# time_circuit_controller_1_1.net
KiCad netlist of a schematic drawn in EAGLE
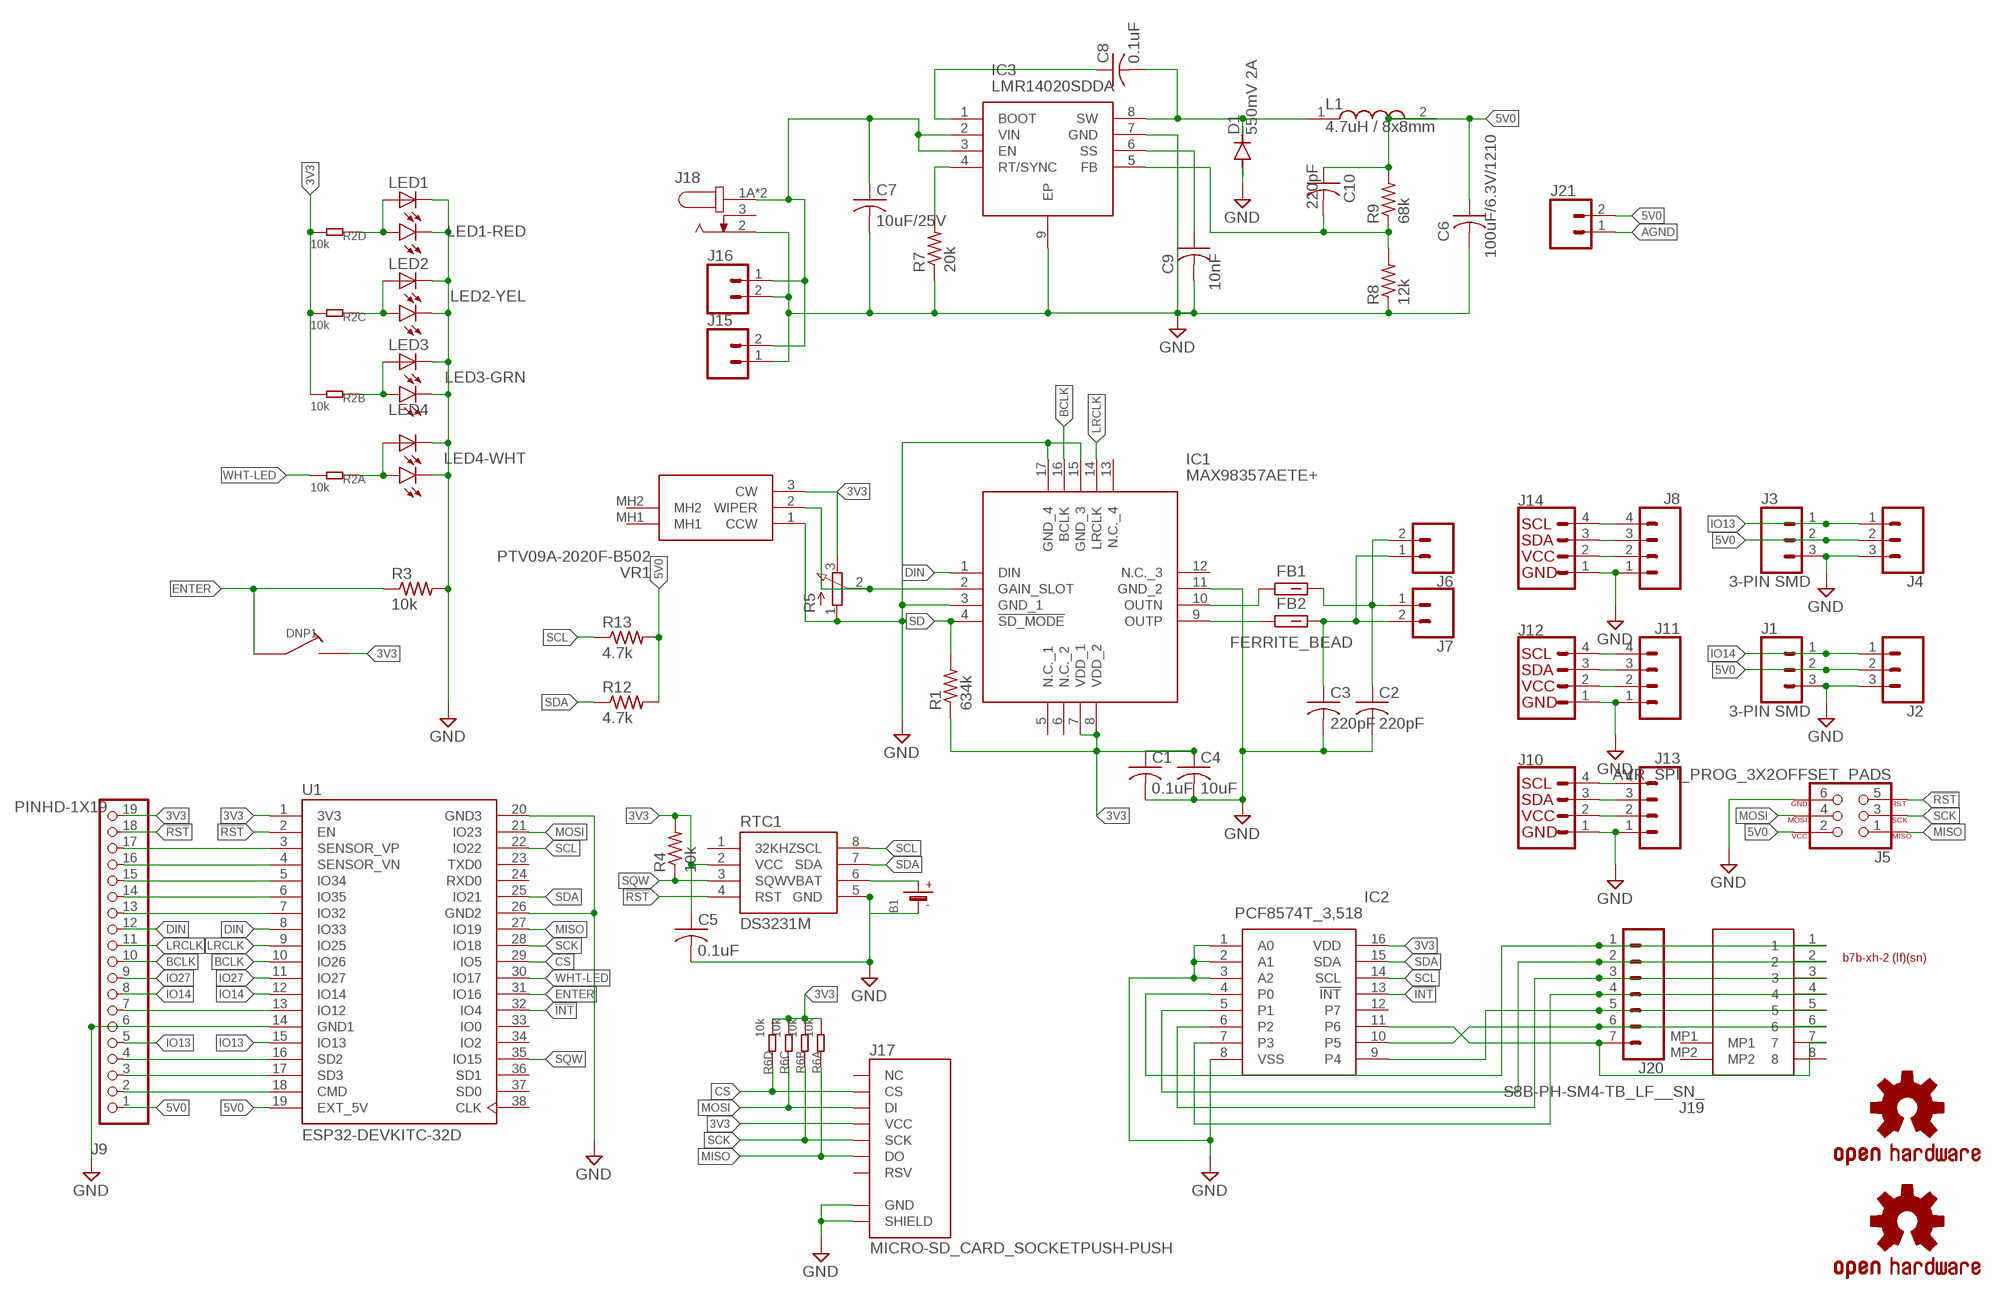
[diagram p0: schematic, sheet 1]

(export (version "E")
  (design (tool "Eeschema 10.0.6"))
  (components
    (comp (ref "B1")
      (value "BATTERYCR2032_BAT-HLD-001")
      (footprint "eagle-import:CR2032_SMT_BAT-HLD-001")
      (libsource (lib "eagle-import") (part "BATTERYCR2032_BAT-HLD-001"))
    )
    (comp (ref "C1")
      (value "0.1uF")
      (footprint "eagle-import:C0603")
      (libsource (lib "eagle-import") (part "C-USC0603"))
    )
    (comp (ref "C2")
      (value "220pF")
      (footprint "eagle-import:C0603")
      (libsource (lib "eagle-import") (part "C-USC0603"))
    )
    (comp (ref "C3")
      (value "220pF")
      (footprint "eagle-import:C0603")
      (libsource (lib "eagle-import") (part "C-USC0603"))
    )
    (comp (ref "C4")
      (value "10uF")
      (footprint "eagle-import:C0603")
      (libsource (lib "eagle-import") (part "C-USC0603"))
    )
    (comp (ref "C5")
      (value "0.1uF")
      (footprint "eagle-import:C0603")
      (libsource (lib "eagle-import") (part "C-USC0603"))
    )
    (comp (ref "C6")
      (value "100uF/6.3V/1210")
      (footprint "eagle-import:C1210")
      (libsource (lib "eagle-import") (part "C-USC1210"))
    )
    (comp (ref "C7")
      (value "10uF/25V")
      (footprint "eagle-import:C0805")
      (libsource (lib "eagle-import") (part "C-USC0805"))
    )
    (comp (ref "C8")
      (value "0.1uF")
      (footprint "eagle-import:C0603")
      (libsource (lib "eagle-import") (part "C-USC0603"))
    )
    (comp (ref "C9")
      (value "10nF")
      (footprint "eagle-import:C0603")
      (libsource (lib "eagle-import") (part "C-USC0603"))
    )
    (comp (ref "C10")
      (value "220pF")
      (footprint "eagle-import:C0603")
      (libsource (lib "eagle-import") (part "C-USC0603"))
    )
    (comp (ref "D1")
      (value "550mV 2A")
      (footprint "eagle-import:DO214AC")
      (libsource (lib "eagle-import") (part "DIODE-DO214AC"))
    )
    (comp (ref "DNP1")
      (value "SWITCH-PINHEAD")
      (footprint "eagle-import:PIN-1X2-3.5MM")
      (libsource (lib "eagle-import") (part "SWITCH-PINHEAD"))
    )
    (comp (ref "FB1")
      (value "FERRITE_BEAD")
      (footprint "eagle-import:BEADC1608X95N")
      (libsource (lib "eagle-import") (part "FBCHIP-0603(1608-METRIC)"))
    )
    (comp (ref "FB2")
      (value "FERRITE_BEAD")
      (footprint "eagle-import:BEADC1608X95N")
      (libsource (lib "eagle-import") (part "FBCHIP-0603(1608-METRIC)"))
    )
    (comp (ref "IC1")
      (value "MAX98357AETE+")
      (footprint "eagle-import:QFN50P300X300X80-17N")
      (fields (field (name "MOUSER_PART_NUMBER") "700-MAX98357AETE+"))
      (libsource (lib "eagle-import") (part "MAX98357AETE+"))
    )
    (comp (ref "IC2")
      (value "PCF8574T_3,518")
      (footprint "eagle-import:SOIC127P1032X265-16N")
      (fields
        (field (name "ARROW_PART_NUMBER") "PCF8574T/3,518")
        (field (name "MOUSER_PART_NUMBER") "771-PCF8574TD-T")
      )
      (libsource (lib "eagle-import") (part "PCF8574T_3,518"))
    )
    (comp (ref "IC3")
      (value "LMR14020SDDA")
      (footprint "eagle-import:SOIC127P600X170-9N")
      (fields
        (field (name "MOUSER_PART_NUMBER") "595-LMR14020SDDA")
        (field (name "RS_PART_NUMBER") "1629813")
      )
      (libsource (lib "eagle-import") (part "LMR14020SDDA"))
    )
    (comp (ref "J1")
      (value "3-PIN SMD")
      (footprint "eagle-import:JST-3-SMD")
      (libsource (lib "eagle-import") (part "CONN_03JST-SMD"))
    )
    (comp (ref "J2")
      (value "CONN_03LOCK_LONGPADS")
      (footprint "eagle-import:1X03_LOCK_LONGPADS")
      (libsource (lib "eagle-import") (part "CONN_03LOCK_LONGPADS"))
    )
    (comp (ref "J3")
      (value "3-PIN SMD")
      (footprint "eagle-import:JST-3-SMD")
      (libsource (lib "eagle-import") (part "CONN_03JST-SMD"))
    )
    (comp (ref "J4")
      (value "CONN_03LOCK_LONGPADS")
      (footprint "eagle-import:1X03_LOCK_LONGPADS")
      (libsource (lib "eagle-import") (part "CONN_03LOCK_LONGPADS"))
    )
    (comp (ref "J5")
      (value "AVR_SPI_PROG_3X2OFFSET_PADS")
      (footprint "eagle-import:2X3_OFFSET")
      (libsource (lib "eagle-import") (part "AVR_SPI_PROG_3X2OFFSET_PADS"))
    )
    (comp (ref "J6")
      (value "CONN_02-JST-2MM-SMT")
      (footprint "eagle-import:JST-2-SMD")
      (libsource (lib "eagle-import") (part "SparkFun-Connectors_8231346_CONN_02-JST-2MM-SMT"))
    )
    (comp (ref "J7")
      (value "CONN_02")
      (footprint "eagle-import:1X02")
      (libsource (lib "eagle-import") (part "CONN_02"))
    )
    (comp (ref "J8")
      (value "CONN_04SMD_2.54")
      (footprint "eagle-import:1X04_5.5MM_STRAIGHT")
      (libsource (lib "eagle-import") (part "CONN_04SMD_2.54"))
    )
    (comp (ref "J9")
      (value "PINHD-1X19")
      (footprint "eagle-import:1X19")
      (libsource (lib "eagle-import") (part "PINHD-1X19"))
    )
    (comp (ref "J10")
      (value "I2C_STANDARD")
      (footprint "eagle-import:1X04")
      (libsource (lib "eagle-import") (part "I2C_STANDARD"))
    )
    (comp (ref "J11")
      (value "CONN_04SMD_2.54")
      (footprint "eagle-import:1X04_5.5MM_STRAIGHT")
      (libsource (lib "eagle-import") (part "CONN_04SMD_2.54"))
    )
    (comp (ref "J12")
      (value "I2C_STANDARD")
      (footprint "eagle-import:1X04")
      (libsource (lib "eagle-import") (part "I2C_STANDARD"))
    )
    (comp (ref "J13")
      (value "CONN_04SMD_2.54")
      (footprint "eagle-import:1X04_5.5MM_STRAIGHT")
      (libsource (lib "eagle-import") (part "CONN_04SMD_2.54"))
    )
    (comp (ref "J14")
      (value "I2C_STANDARD")
      (footprint "eagle-import:1X04")
      (libsource (lib "eagle-import") (part "I2C_STANDARD"))
    )
    (comp (ref "J15")
      (value "CONN_023.5MM")
      (footprint "eagle-import:SCREWTERMINAL-3.5MM-2")
      (libsource (lib "eagle-import") (part "SparkFun-Connectors_8231346_CONN_023.5MM"))
    )
    (comp (ref "J16")
      (value "CONN_02-JST-2MM-SMT")
      (footprint "eagle-import:JST-2-SMD")
      (libsource (lib "eagle-import") (part "SparkFun-Connectors_8231346_CONN_02-JST-2MM-SMT"))
    )
    (comp (ref "J17")
      (value "MICRO-SD_CARD_SOCKETPUSH-PUSH")
      (footprint "eagle-import:MICRO-SD-SOCKET")
      (libsource (lib "eagle-import") (part "MICRO-SD_CARD_SOCKETPUSH-PUSH"))
    )
    (comp (ref "J18")
      (value "9-12VAC")
      (footprint "eagle-import:CUI_PJ-002AH-SMT-TR")
      (fields (field (name "MF") "CUI") (field (name "MP") "PJ-002AH-SMT-TR"))
      (libsource (lib "eagle-import") (part "PJ-002AH-SMT-TR"))
    )
    (comp (ref "J19")
      (value "S8B-PH-SM4-TB_LF__SN_")
      (footprint "eagle-import:S8BPHSM4TBLFSN")
      (fields (field (name "ARROW_PART_NUMBER") "S8B-PH-SM4-TB(LF)(SN)"))
      (libsource (lib "eagle-import") (part "S8B-PH-SM4-TB_LF__SN_"))
    )
    (comp (ref "J20")
      (value "CONN_07LOCK")
      (footprint "eagle-import:1X07_LOCK")
      (libsource (lib "eagle-import") (part "CONN_07LOCK"))
    )
    (comp (ref "J21")
      (value "CONN_023.5MM")
      (footprint "eagle-import:SCREWTERMINAL-3.5MM-2")
      (libsource (lib "eagle-import") (part "SparkFun-Connectors_8231346_CONN_023.5MM"))
    )
    (comp (ref "L1")
      (value "4.7uH / 8x8mm")
      (footprint "eagle-import:INDPM8082X300N")
      (fields (field (name "MANUFACTURER_PART_NUMBER") "1273AS-H-3R3N=P3"))
      (libsource (lib "eagle-import") (part "1273AS-H-3R3N=P3"))
    )
    (comp (ref "LED1")
      (value "LEDCHIPLED_1206")
      (footprint "eagle-import:CHIPLED_1206")
      (libsource (lib "eagle-import") (part "LEDCHIPLED_1206"))
    )
    (comp (ref "LED1-RED")
      (value "LED5MM")
      (footprint "eagle-import:LED5MM")
      (libsource (lib "eagle-import") (part "led_259_LED5MM"))
    )
    (comp (ref "LED2")
      (value "LEDCHIPLED_1206")
      (footprint "eagle-import:CHIPLED_1206")
      (libsource (lib "eagle-import") (part "LEDCHIPLED_1206"))
    )
    (comp (ref "LED2-YEL")
      (value "LED5MM")
      (footprint "eagle-import:LED5MM")
      (libsource (lib "eagle-import") (part "led_259_LED5MM"))
    )
    (comp (ref "LED3")
      (value "LEDCHIPLED_1206")
      (footprint "eagle-import:CHIPLED_1206")
      (libsource (lib "eagle-import") (part "LEDCHIPLED_1206"))
    )
    (comp (ref "LED3-GRN")
      (value "LED5MM")
      (footprint "eagle-import:LED5MM")
      (libsource (lib "eagle-import") (part "led_259_LED5MM"))
    )
    (comp (ref "LED4")
      (value "LEDCHIPLED_1206")
      (footprint "eagle-import:CHIPLED_1206")
      (libsource (lib "eagle-import") (part "LEDCHIPLED_1206"))
    )
    (comp (ref "LED4-WHT")
      (value "LED5MM")
      (footprint "eagle-import:LED5MM")
      (libsource (lib "eagle-import") (part "led_259_LED5MM"))
    )
    (comp (ref "LOGO1")
      (value "OSHW-LOGOL")
      (footprint "eagle-import:OSHW-LOGO-L")
      (libsource (lib "eagle-import") (part "OSHW-LOGOL"))
    )
    (comp (ref "LOGO2")
      (value "OSHW-LOGOL")
      (footprint "eagle-import:OSHW-LOGO-L")
      (libsource (lib "eagle-import") (part "OSHW-LOGOL"))
    )
    (comp (ref "R1")
      (value "634k")
      (footprint "eagle-import:R0603")
      (libsource (lib "eagle-import") (part "R-US_R0603"))
    )
    (comp (ref "R2")
      (value "10k")
      (footprint "eagle-import:RA1206-8")
      (libsource (lib "eagle-import") (part "RES-ARRAY-1206"))
    )
    (comp (ref "R3")
      (value "10k")
      (footprint "eagle-import:R0603")
      (libsource (lib "eagle-import") (part "R-US_R0603"))
    )
    (comp (ref "R4")
      (value "10k")
      (footprint "eagle-import:R0603")
      (libsource (lib "eagle-import") (part "R-US_R0603"))
    )
    (comp (ref "R5")
      (value "3RP/1610N")
      (footprint "eagle-import:3RP_1610N")
      (libsource (lib "eagle-import") (part "3RP/1610N"))
    )
    (comp (ref "R6")
      (value "10k")
      (footprint "eagle-import:RA1206-8")
      (libsource (lib "eagle-import") (part "RES-ARRAY-1206"))
    )
    (comp (ref "R7")
      (value "20k")
      (footprint "eagle-import:R0603")
      (libsource (lib "eagle-import") (part "R-US_R0603"))
    )
    (comp (ref "R8")
      (value "12k")
      (footprint "eagle-import:R0603")
      (libsource (lib "eagle-import") (part "R-US_R0603"))
    )
    (comp (ref "R9")
      (value "68k")
      (footprint "eagle-import:R0603")
      (libsource (lib "eagle-import") (part "R-US_R0603"))
    )
    (comp (ref "R12")
      (value "4.7k")
      (footprint "eagle-import:R0603")
      (libsource (lib "eagle-import") (part "R-US_R0603"))
    )
    (comp (ref "R13")
      (value "4.7k")
      (footprint "eagle-import:R0603")
      (libsource (lib "eagle-import") (part "R-US_R0603"))
    )
    (comp (ref "RTC1")
      (value "DS3231M")
      (footprint "eagle-import:SO08")
      (libsource (lib "eagle-import") (part "DS3231M"))
    )
    (comp (ref "U1")
      (value "ESP32-DEVKITC-32D")
      (footprint "eagle-import:MODULE_ESP32-DEVKITC-32D")
      (fields (field (name "MF") "Espressif Systems"))
      (libsource (lib "eagle-import") (part "ESP32-DEVKITC-32D"))
    )
    (comp (ref "VR1")
      (value "PTV09A-2020F-B502")
      (footprint "eagle-import:PTV09A2020FB502")
      (fields (field (name "MOUSER_PART_NUMBER") "652-PTV09A-2020FB502"))
      (libsource (lib "eagle-import") (part "PTV09A-2020F-B502"))
    )
  )
  (nets
    (net (code "1") (name "3V3") (class "Default")
      (node (ref "C1") (pin "1") (pinfunction "1_1") (pintype "passive"))
      (node (ref "C4") (pin "1") (pinfunction "1_1") (pintype "passive"))
      (node (ref "C5") (pin "1") (pinfunction "1_1") (pintype "passive"))
      (node (ref "DNP1") (pin "P$2") (pinfunction "2_P$2") (pintype "bidirectional"))
      (node (ref "IC1") (pin "7") (pinfunction "VDD_1_7") (pintype "bidirectional"))
      (node (ref "IC1") (pin "8") (pinfunction "VDD_2_8") (pintype "bidirectional"))
      (node (ref "IC2") (pin "16") (pinfunction "VDD_16") (pintype "bidirectional"))
      (node (ref "J17") (pin "VCC") (pinfunction "VCC_VCC") (pintype "bidirectional"))
      (node (ref "J9") (pin "19") (pinfunction "19_19") (pintype "passive"))
      (node (ref "R1") (pin "1") (pinfunction "1_1") (pintype "passive"))
      (node (ref "R2") (pin "2") (pinfunction "1_2") (pintype "passive"))
      (node (ref "R2") (pin "3") (pinfunction "1_3") (pintype "passive"))
      (node (ref "R2") (pin "4") (pinfunction "1_4") (pintype "passive"))
      (node (ref "R4") (pin "2") (pinfunction "2_2") (pintype "passive"))
      (node (ref "R5") (pin "3") (pinfunction "E_3") (pintype "passive"))
      (node (ref "R6") (pin "1") (pinfunction "1_1") (pintype "passive"))
      (node (ref "R6") (pin "2") (pinfunction "1_2") (pintype "passive"))
      (node (ref "R6") (pin "3") (pinfunction "1_3") (pintype "passive"))
      (node (ref "R6") (pin "4") (pinfunction "1_4") (pintype "passive"))
      (node (ref "RTC1") (pin "2") (pinfunction "VCC_2") (pintype "power_in"))
      (node (ref "U1") (pin "1") (pinfunction "3V3_1") (pintype "power_in"))
      (node (ref "VR1") (pin "3") (pinfunction "CW_3") (pintype "bidirectional"))
    )
    (net (code "2") (name "5V0") (class "Default")
      (node (ref "C10") (pin "1") (pinfunction "1_1") (pintype "passive"))
      (node (ref "C6") (pin "1") (pinfunction "1_1") (pintype "passive"))
      (node (ref "J1") (pin "2") (pinfunction "2_2") (pintype "passive"))
      (node (ref "J10") (pin "2") (pinfunction "2_2") (pintype "power_in"))
      (node (ref "J11") (pin "2") (pinfunction "2_2") (pintype "passive"))
      (node (ref "J12") (pin "2") (pinfunction "2_2") (pintype "power_in"))
      (node (ref "J13") (pin "2") (pinfunction "2_2") (pintype "passive"))
      (node (ref "J14") (pin "2") (pinfunction "2_2") (pintype "power_in"))
      (node (ref "J2") (pin "2") (pinfunction "2_2") (pintype "passive"))
      (node (ref "J21") (pin "2") (pinfunction "2_2") (pintype "passive"))
      (node (ref "J3") (pin "2") (pinfunction "2_2") (pintype "passive"))
      (node (ref "J4") (pin "2") (pinfunction "2_2") (pintype "passive"))
      (node (ref "J5") (pin "2") (pinfunction "2_2") (pintype "passive"))
      (node (ref "J8") (pin "2") (pinfunction "2_2") (pintype "passive"))
      (node (ref "J9") (pin "1") (pinfunction "1_1") (pintype "passive"))
      (node (ref "L1") (pin "2") (pinfunction "2_2") (pintype "power_in"))
      (node (ref "R12") (pin "2") (pinfunction "2_2") (pintype "passive"))
      (node (ref "R13") (pin "2") (pinfunction "2_2") (pintype "passive"))
      (node (ref "R9") (pin "2") (pinfunction "2_2") (pintype "passive"))
      (node (ref "U1") (pin "19") (pinfunction "EXT_5V_19") (pintype "power_in"))
    )
    (net (code "3") (name "AGND") (class "Default")
      (node (ref "B1") (pin "-") (pinfunction "-_-") (pintype "passive"))
      (node (ref "C1") (pin "2") (pinfunction "2_2") (pintype "passive"))
      (node (ref "C2") (pin "2") (pinfunction "2_2") (pintype "passive"))
      (node (ref "C3") (pin "2") (pinfunction "2_2") (pintype "passive"))
      (node (ref "C4") (pin "2") (pinfunction "2_2") (pintype "passive"))
      (node (ref "C5") (pin "2") (pinfunction "2_2") (pintype "passive"))
      (node (ref "C6") (pin "2") (pinfunction "2_2") (pintype "passive"))
      (node (ref "C7") (pin "2") (pinfunction "2_2") (pintype "passive"))
      (node (ref "C9") (pin "2") (pinfunction "2_2") (pintype "passive"))
      (node (ref "D1") (pin "A") (pinfunction "A_A") (pintype "passive"))
      (node (ref "IC1") (pin "11") (pinfunction "GND_2_11") (pintype "bidirectional"))
      (node (ref "IC1") (pin "15") (pinfunction "GND_3_15") (pintype "bidirectional"))
      (node (ref "IC1") (pin "17") (pinfunction "GND_4_17") (pintype "bidirectional"))
      (node (ref "IC1") (pin "3") (pinfunction "GND_1_3") (pintype "bidirectional"))
      (node (ref "IC2") (pin "1") (pinfunction "A0_1") (pintype "bidirectional"))
      (node (ref "IC2") (pin "2") (pinfunction "A1_2") (pintype "bidirectional"))
      (node (ref "IC2") (pin "3") (pinfunction "A2_3") (pintype "bidirectional"))
      (node (ref "IC2") (pin "8") (pinfunction "VSS_8") (pintype "bidirectional"))
      (node (ref "IC3") (pin "7") (pinfunction "GND_7") (pintype "power_in"))
      (node (ref "IC3") (pin "9") (pinfunction "EP_9") (pintype "power_in"))
      (node (ref "J1") (pin "3") (pinfunction "1_3") (pintype "passive"))
      (node (ref "J10") (pin "1") (pinfunction "1_1") (pintype "power_in"))
      (node (ref "J11") (pin "1") (pinfunction "1_1") (pintype "passive"))
      (node (ref "J12") (pin "1") (pinfunction "1_1") (pintype "power_in"))
      (node (ref "J13") (pin "1") (pinfunction "1_1") (pintype "passive"))
      (node (ref "J14") (pin "1") (pinfunction "1_1") (pintype "power_in"))
      (node (ref "J15") (pin "1") (pinfunction "1_1") (pintype "passive"))
      (node (ref "J16") (pin "2") (pinfunction "1_2") (pintype "passive"))
      (node (ref "J17") (pin "CD1") (pinfunction "SHIELD_CD1") (pintype "bidirectional"))
      (node (ref "J17") (pin "GND") (pinfunction "GND_GND") (pintype "bidirectional"))
      (node (ref "J18") (pin "2") (pinfunction "2_2") (pintype "passive"))
      (node (ref "J2") (pin "3") (pinfunction "3_3") (pintype "passive"))
      (node (ref "J21") (pin "1") (pinfunction "1_1") (pintype "passive"))
      (node (ref "J3") (pin "3") (pinfunction "1_3") (pintype "passive"))
      (node (ref "J4") (pin "3") (pinfunction "3_3") (pintype "passive"))
      (node (ref "J5") (pin "6") (pinfunction "6_6") (pintype "passive"))
      (node (ref "J8") (pin "1") (pinfunction "1_1") (pintype "passive"))
      (node (ref "J9") (pin "6") (pinfunction "6_6") (pintype "passive"))
      (node (ref "LED1") (pin "C") (pinfunction "C_C") (pintype "passive"))
      (node (ref "LED1-RED") (pin "K") (pinfunction "C_K") (pintype "passive"))
      (node (ref "LED2") (pin "C") (pinfunction "C_C") (pintype "passive"))
      (node (ref "LED2-YEL") (pin "K") (pinfunction "C_K") (pintype "passive"))
      (node (ref "LED3") (pin "C") (pinfunction "C_C") (pintype "passive"))
      (node (ref "LED3-GRN") (pin "K") (pinfunction "C_K") (pintype "passive"))
      (node (ref "LED4") (pin "C") (pinfunction "C_C") (pintype "passive"))
      (node (ref "LED4-WHT") (pin "K") (pinfunction "C_K") (pintype "passive"))
      (node (ref "R3") (pin "2") (pinfunction "2_2") (pintype "passive"))
      (node (ref "R5") (pin "1") (pinfunction "A_1") (pintype "passive"))
      (node (ref "R7") (pin "1") (pinfunction "1_1") (pintype "passive"))
      (node (ref "R8") (pin "1") (pinfunction "1_1") (pintype "passive"))
      (node (ref "RTC1") (pin "5") (pinfunction "GND_5") (pintype "power_in"))
      (node (ref "U1") (pin "14") (pinfunction "GND1_14") (pintype "power_in"))
      (node (ref "U1") (pin "20") (pinfunction "GND3_20") (pintype "power_in"))
      (node (ref "U1") (pin "26") (pinfunction "GND2_26") (pintype "power_in"))
      (node (ref "VR1") (pin "1") (pinfunction "CCW_1") (pintype "bidirectional"))
    )
    (net (code "4") (name "BCLK") (class "Default")
      (node (ref "IC1") (pin "16") (pinfunction "BCLK_16") (pintype "bidirectional"))
      (node (ref "J9") (pin "10") (pinfunction "10_10") (pintype "passive"))
      (node (ref "U1") (pin "10") (pinfunction "IO26_10") (pintype "bidirectional"))
    )
    (net (code "5") (name "CS") (class "Default")
      (node (ref "J17") (pin "CS") (pinfunction "CS_CS") (pintype "bidirectional"))
      (node (ref "R6") (pin "5") (pinfunction "2_5") (pintype "passive"))
      (node (ref "U1") (pin "29") (pinfunction "IO5_29") (pintype "bidirectional"))
    )
    (net (code "6") (name "DIN") (class "Default")
      (node (ref "IC1") (pin "1") (pinfunction "DIN_1") (pintype "bidirectional"))
      (node (ref "J9") (pin "12") (pinfunction "12_12") (pintype "passive"))
      (node (ref "U1") (pin "8") (pinfunction "IO33_8") (pintype "bidirectional"))
    )
    (net (code "7") (name "ENTER") (class "Default")
      (node (ref "DNP1") (pin "P$1") (pinfunction "1_P$1") (pintype "bidirectional"))
      (node (ref "R3") (pin "1") (pinfunction "1_1") (pintype "passive"))
      (node (ref "U1") (pin "31") (pinfunction "IO16_31") (pintype "bidirectional"))
    )
    (net (code "8") (name "IO13") (class "Default")
      (node (ref "J3") (pin "1") (pinfunction "3_1") (pintype "passive"))
      (node (ref "J4") (pin "1") (pinfunction "1_1") (pintype "passive"))
      (node (ref "J9") (pin "5") (pinfunction "5_5") (pintype "passive"))
      (node (ref "U1") (pin "15") (pinfunction "IO13_15") (pintype "bidirectional"))
    )
    (net (code "9") (name "IO14") (class "Default")
      (node (ref "J1") (pin "1") (pinfunction "3_1") (pintype "passive"))
      (node (ref "J2") (pin "1") (pinfunction "1_1") (pintype "passive"))
      (node (ref "J9") (pin "8") (pinfunction "8_8") (pintype "passive"))
      (node (ref "U1") (pin "12") (pinfunction "IO14_12") (pintype "bidirectional"))
    )
    (net (code "10") (name "IO27") (class "Default")
      (node (ref "J9") (pin "9") (pinfunction "9_9") (pintype "passive"))
      (node (ref "U1") (pin "11") (pinfunction "IO27_11") (pintype "bidirectional"))
    )
    (net (code "11") (name "LRCLK") (class "Default")
      (node (ref "IC1") (pin "14") (pinfunction "LRCLK_14") (pintype "bidirectional"))
      (node (ref "J9") (pin "11") (pinfunction "11_11") (pintype "passive"))
      (node (ref "U1") (pin "9") (pinfunction "IO25_9") (pintype "bidirectional"))
    )
    (net (code "12") (name "MISO") (class "Default")
      (node (ref "J17") (pin "DO") (pinfunction "DO_DO") (pintype "bidirectional"))
      (node (ref "J5") (pin "1") (pinfunction "1_1") (pintype "passive"))
      (node (ref "R6") (pin "8") (pinfunction "2_8") (pintype "passive"))
      (node (ref "U1") (pin "27") (pinfunction "IO19_27") (pintype "bidirectional"))
    )
    (net (code "13") (name "MOSI") (class "Default")
      (node (ref "J17") (pin "DI") (pinfunction "DI_DI") (pintype "bidirectional"))
      (node (ref "J5") (pin "4") (pinfunction "4_4") (pintype "passive"))
      (node (ref "R6") (pin "6") (pinfunction "2_6") (pintype "passive"))
      (node (ref "U1") (pin "21") (pinfunction "IO23_21") (pintype "bidirectional"))
    )
    (net (code "14") (name "Net-(IC1-GAIN_SLOT)") (class "Default")
      (node (ref "IC1") (pin "2") (pinfunction "GAIN_SLOT_2") (pintype "bidirectional"))
      (node (ref "R5") (pin "2") (pinfunction "S_2") (pintype "passive"))
      (node (ref "VR1") (pin "2") (pinfunction "WIPER_2") (pintype "bidirectional"))
    )
    (net (code "15") (name "Net-(IC1-OUTN)") (class "Default")
      (node (ref "FB1") (pin "1") (pinfunction "1_1") (pintype "passive"))
      (node (ref "IC1") (pin "10") (pinfunction "OUTN_10") (pintype "bidirectional"))
    )
    (net (code "16") (name "Net-(IC1-OUTP)") (class "Default")
      (node (ref "FB2") (pin "1") (pinfunction "1_1") (pintype "passive"))
      (node (ref "IC1") (pin "9") (pinfunction "OUTP_9") (pintype "bidirectional"))
    )
    (net (code "17") (name "Net-(IC2-P0)") (class "Default")
      (node (ref "IC2") (pin "4") (pinfunction "P0_4") (pintype "bidirectional"))
      (node (ref "J19") (pin "1") (pinfunction "1_1") (pintype "bidirectional"))
      (node (ref "J20") (pin "1") (pinfunction "1_1") (pintype "passive"))
    )
    (net (code "18") (name "Net-(IC2-P1)") (class "Default")
      (node (ref "IC2") (pin "5") (pinfunction "P1_5") (pintype "bidirectional"))
      (node (ref "J19") (pin "2") (pinfunction "2_2") (pintype "bidirectional"))
      (node (ref "J20") (pin "2") (pinfunction "2_2") (pintype "passive"))
    )
    (net (code "19") (name "Net-(IC2-P2)") (class "Default")
      (node (ref "IC2") (pin "6") (pinfunction "P2_6") (pintype "bidirectional"))
      (node (ref "J19") (pin "3") (pinfunction "3_3") (pintype "bidirectional"))
      (node (ref "J20") (pin "3") (pinfunction "3_3") (pintype "passive"))
    )
    (net (code "20") (name "Net-(IC2-P3)") (class "Default")
      (node (ref "IC2") (pin "7") (pinfunction "P3_7") (pintype "bidirectional"))
      (node (ref "J19") (pin "4") (pinfunction "4_4") (pintype "bidirectional"))
      (node (ref "J20") (pin "4") (pinfunction "4_4") (pintype "passive"))
    )
    (net (code "21") (name "Net-(IC2-P4)") (class "Default")
      (node (ref "IC2") (pin "9") (pinfunction "P4_9") (pintype "bidirectional"))
      (node (ref "J19") (pin "5") (pinfunction "5_5") (pintype "bidirectional"))
      (node (ref "J20") (pin "5") (pinfunction "5_5") (pintype "passive"))
    )
    (net (code "22") (name "Net-(IC2-P5)") (class "Default")
      (node (ref "IC2") (pin "10") (pinfunction "P5_10") (pintype "bidirectional"))
      (node (ref "J19") (pin "6") (pinfunction "6_6") (pintype "bidirectional"))
      (node (ref "J20") (pin "6") (pinfunction "6_6") (pintype "passive"))
    )
    (net (code "23") (name "Net-(IC2-P6)") (class "Default")
      (node (ref "IC2") (pin "11") (pinfunction "P6_11") (pintype "bidirectional"))
      (node (ref "J19") (pin "7") (pinfunction "7_7") (pintype "bidirectional"))
      (node (ref "J20") (pin "7") (pinfunction "7_7") (pintype "passive"))
    )
    (net (code "24") (name "Net-(IC3-BOOT)") (class "Default")
      (node (ref "C8") (pin "1") (pinfunction "1_1") (pintype "passive"))
      (node (ref "IC3") (pin "1") (pinfunction "BOOT_1") (pintype "bidirectional"))
    )
    (net (code "25") (name "Net-(IC3-EN)") (class "Default")
      (node (ref "C7") (pin "1") (pinfunction "1_1") (pintype "passive"))
      (node (ref "IC3") (pin "2") (pinfunction "VIN_2") (pintype "input"))
      (node (ref "IC3") (pin "3") (pinfunction "EN_3") (pintype "bidirectional"))
      (node (ref "J15") (pin "2") (pinfunction "2_2") (pintype "passive"))
      (node (ref "J16") (pin "1") (pinfunction "2_1") (pintype "passive"))
      (node (ref "J18") (pin "1A") (pinfunction "1_1A") (pintype "passive"))
      (node (ref "J18") (pin "1B") (pinfunction "1_1B") (pintype "passive"))
    )
    (net (code "26") (name "Net-(IC3-FB)") (class "Default")
      (node (ref "C10") (pin "2") (pinfunction "2_2") (pintype "passive"))
      (node (ref "IC3") (pin "5") (pinfunction "FB_5") (pintype "bidirectional"))
      (node (ref "R8") (pin "2") (pinfunction "2_2") (pintype "passive"))
      (node (ref "R9") (pin "1") (pinfunction "1_1") (pintype "passive"))
    )
    (net (code "27") (name "Net-(IC3-RT{slash}SYNC)") (class "Default")
      (node (ref "IC3") (pin "4") (pinfunction "RT/SYNC_4") (pintype "bidirectional"))
      (node (ref "R7") (pin "2") (pinfunction "2_2") (pintype "passive"))
    )
    (net (code "28") (name "Net-(IC3-SS)") (class "Default")
      (node (ref "C9") (pin "1") (pinfunction "1_1") (pintype "passive"))
      (node (ref "IC3") (pin "6") (pinfunction "SS_6") (pintype "bidirectional"))
    )
    (net (code "29") (name "Net-(IC3-SW)") (class "Default")
      (node (ref "C8") (pin "2") (pinfunction "2_2") (pintype "passive"))
      (node (ref "D1") (pin "C") (pinfunction "C_C") (pintype "passive"))
      (node (ref "IC3") (pin "8") (pinfunction "SW_8") (pintype "bidirectional"))
      (node (ref "L1") (pin "1") (pinfunction "1_1") (pintype "power_in"))
    )
    (net (code "30") (name "Net-(J6-1)") (class "Default")
      (node (ref "C2") (pin "1") (pinfunction "1_1") (pintype "passive"))
      (node (ref "FB1") (pin "2") (pinfunction "2_2") (pintype "passive"))
      (node (ref "J6") (pin "2") (pinfunction "1_2") (pintype "passive"))
      (node (ref "J7") (pin "1") (pinfunction "1_1") (pintype "passive"))
    )
    (net (code "31") (name "Net-(J6-2)") (class "Default")
      (node (ref "C3") (pin "1") (pinfunction "1_1") (pintype "passive"))
      (node (ref "FB2") (pin "2") (pinfunction "2_2") (pintype "passive"))
      (node (ref "J6") (pin "1") (pinfunction "2_1") (pintype "passive"))
      (node (ref "J7") (pin "2") (pinfunction "2_2") (pintype "passive"))
    )
    (net (code "32") (name "Net-(R2A-2)") (class "Default")
      (node (ref "LED4") (pin "A") (pinfunction "A_A") (pintype "passive"))
      (node (ref "LED4-WHT") (pin "A") (pinfunction "A_A") (pintype "passive"))
      (node (ref "R2") (pin "8") (pinfunction "2_8") (pintype "passive"))
    )
    (net (code "33") (name "Net-(R2B-2)") (class "Default")
      (node (ref "LED3") (pin "A") (pinfunction "A_A") (pintype "passive"))
      (node (ref "LED3-GRN") (pin "A") (pinfunction "A_A") (pintype "passive"))
      (node (ref "R2") (pin "7") (pinfunction "2_7") (pintype "passive"))
    )
    (net (code "34") (name "Net-(R2C-2)") (class "Default")
      (node (ref "LED2") (pin "A") (pinfunction "A_A") (pintype "passive"))
      (node (ref "LED2-YEL") (pin "A") (pinfunction "A_A") (pintype "passive"))
      (node (ref "R2") (pin "6") (pinfunction "2_6") (pintype "passive"))
    )
    (net (code "35") (name "Net-(R2D-2)") (class "Default")
      (node (ref "LED1") (pin "A") (pinfunction "A_A") (pintype "passive"))
      (node (ref "LED1-RED") (pin "A") (pinfunction "A_A") (pintype "passive"))
      (node (ref "R2") (pin "5") (pinfunction "2_5") (pintype "passive"))
    )
    (net (code "36") (name "Net-(RTC1-VBAT)") (class "Default")
      (node (ref "B1") (pin "+$1") (pinfunction "+_+$1") (pintype "passive"))
      (node (ref "B1") (pin "+$2") (pinfunction "+_+$2") (pintype "passive"))
      (node (ref "RTC1") (pin "6") (pinfunction "VBAT_6") (pintype "power_in"))
    )
    (net (code "37") (name "Net-(U1-CMD)") (class "Default")
      (node (ref "J9") (pin "2") (pinfunction "2_2") (pintype "passive"))
      (node (ref "U1") (pin "18") (pinfunction "CMD_18") (pintype "bidirectional"))
    )
    (net (code "38") (name "Net-(U1-IO12)") (class "Default")
      (node (ref "J9") (pin "7") (pinfunction "7_7") (pintype "passive"))
      (node (ref "U1") (pin "13") (pinfunction "IO12_13") (pintype "bidirectional"))
    )
    (net (code "39") (name "Net-(U1-IO32)") (class "Default")
      (node (ref "J9") (pin "13") (pinfunction "13_13") (pintype "passive"))
      (node (ref "U1") (pin "7") (pinfunction "IO32_7") (pintype "bidirectional"))
    )
    (net (code "40") (name "Net-(U1-IO34)") (class "Default")
      (node (ref "J9") (pin "15") (pinfunction "15_15") (pintype "passive"))
      (node (ref "U1") (pin "5") (pinfunction "IO34_5") (pintype "bidirectional"))
    )
    (net (code "41") (name "Net-(U1-IO35)") (class "Default")
      (node (ref "J9") (pin "14") (pinfunction "14_14") (pintype "passive"))
      (node (ref "U1") (pin "6") (pinfunction "IO35_6") (pintype "bidirectional"))
    )
    (net (code "42") (name "Net-(U1-SD2)") (class "Default")
      (node (ref "J9") (pin "4") (pinfunction "4_4") (pintype "passive"))
      (node (ref "U1") (pin "16") (pinfunction "SD2_16") (pintype "bidirectional"))
    )
    (net (code "43") (name "Net-(U1-SD3)") (class "Default")
      (node (ref "J9") (pin "3") (pinfunction "3_3") (pintype "passive"))
      (node (ref "U1") (pin "17") (pinfunction "SD3_17") (pintype "bidirectional"))
    )
    (net (code "44") (name "Net-(U1-SENSOR_VN)") (class "Default")
      (node (ref "J9") (pin "16") (pinfunction "16_16") (pintype "passive"))
      (node (ref "U1") (pin "4") (pinfunction "SENSOR_VN_4") (pintype "input"))
    )
    (net (code "45") (name "Net-(U1-SENSOR_VP)") (class "Default")
      (node (ref "J9") (pin "17") (pinfunction "17_17") (pintype "passive"))
      (node (ref "U1") (pin "3") (pinfunction "SENSOR_VP_3") (pintype "input"))
    )
    (net (code "46") (name "SCK") (class "Default")
      (node (ref "J17") (pin "SCLK") (pinfunction "SCK_SCLK") (pintype "bidirectional"))
      (node (ref "J5") (pin "3") (pinfunction "3_3") (pintype "passive"))
      (node (ref "R6") (pin "7") (pinfunction "2_7") (pintype "passive"))
      (node (ref "U1") (pin "28") (pinfunction "IO18_28") (pintype "bidirectional"))
    )
    (net (code "47") (name "SCL") (class "Default")
      (node (ref "IC2") (pin "14") (pinfunction "SCL_14") (pintype "bidirectional"))
      (node (ref "J10") (pin "4") (pinfunction "4_4") (pintype "passive"))
      (node (ref "J11") (pin "4") (pinfunction "4_4") (pintype "passive"))
      (node (ref "J12") (pin "4") (pinfunction "4_4") (pintype "passive"))
      (node (ref "J13") (pin "4") (pinfunction "4_4") (pintype "passive"))
      (node (ref "J14") (pin "4") (pinfunction "4_4") (pintype "passive"))
      (node (ref "J8") (pin "4") (pinfunction "4_4") (pintype "passive"))
      (node (ref "R13") (pin "1") (pinfunction "1_1") (pintype "passive"))
      (node (ref "RTC1") (pin "8") (pinfunction "SCL_8") (pintype "bidirectional"))
      (node (ref "U1") (pin "22") (pinfunction "IO22_22") (pintype "bidirectional"))
    )
    (net (code "48") (name "SD") (class "Default")
      (node (ref "IC1") (pin "4") (pinfunction "~{SD_MODE}_4") (pintype "bidirectional"))
      (node (ref "R1") (pin "2") (pinfunction "2_2") (pintype "passive"))
    )
    (net (code "49") (name "SDA") (class "Default")
      (node (ref "IC2") (pin "15") (pinfunction "SDA_15") (pintype "bidirectional"))
      (node (ref "J10") (pin "3") (pinfunction "3_3") (pintype "passive"))
      (node (ref "J11") (pin "3") (pinfunction "3_3") (pintype "passive"))
      (node (ref "J12") (pin "3") (pinfunction "3_3") (pintype "passive"))
      (node (ref "J13") (pin "3") (pinfunction "3_3") (pintype "passive"))
      (node (ref "J14") (pin "3") (pinfunction "3_3") (pintype "passive"))
      (node (ref "J8") (pin "3") (pinfunction "3_3") (pintype "passive"))
      (node (ref "R12") (pin "1") (pinfunction "1_1") (pintype "passive"))
      (node (ref "RTC1") (pin "7") (pinfunction "SDA_7") (pintype "bidirectional"))
      (node (ref "U1") (pin "25") (pinfunction "IO21_25") (pintype "bidirectional"))
    )
    (net (code "50") (name "SQW") (class "Default")
      (node (ref "R4") (pin "1") (pinfunction "1_1") (pintype "passive"))
      (node (ref "RTC1") (pin "3") (pinfunction "SQW_3") (pintype "output"))
      (node (ref "U1") (pin "35") (pinfunction "IO15_35") (pintype "bidirectional"))
    )
    (net (code "51") (name "WHT-LED") (class "Default")
      (node (ref "R2") (pin "1") (pinfunction "1_1") (pintype "passive"))
      (node (ref "U1") (pin "30") (pinfunction "IO17_30") (pintype "bidirectional"))
    )
    (net (code "52") (name "unconnected-(IC1-N.C._1-Pad5)") (class "Default")
      (node (ref "IC1") (pin "5") (pinfunction "N.C._1_5") (pintype "bidirectional"))
    )
    (net (code "53") (name "unconnected-(IC1-N.C._2-Pad6)") (class "Default")
      (node (ref "IC1") (pin "6") (pinfunction "N.C._2_6") (pintype "bidirectional"))
    )
    (net (code "54") (name "unconnected-(IC1-N.C._3-Pad12)") (class "Default")
      (node (ref "IC1") (pin "12") (pinfunction "N.C._3_12") (pintype "bidirectional"))
    )
    (net (code "55") (name "unconnected-(IC1-N.C._4-Pad13)") (class "Default")
      (node (ref "IC1") (pin "13") (pinfunction "N.C._4_13") (pintype "bidirectional"))
    )
    (net (code "56") (name "unconnected-(IC2-P7-Pad12)") (class "Default")
      (node (ref "IC2") (pin "12") (pinfunction "P7_12") (pintype "bidirectional"))
    )
    (net (code "57") (name "unconnected-(J17-NC-PadRSV2)") (class "Default")
      (node (ref "J17") (pin "RSV2") (pinfunction "NC_RSV2") (pintype "bidirectional"))
    )
    (net (code "58") (name "unconnected-(J17-RSV-PadRSV1)") (class "Default")
      (node (ref "J17") (pin "RSV1") (pinfunction "RSV_RSV1") (pintype "bidirectional"))
    )
    (net (code "59") (name "unconnected-(J18-Pad3)") (class "Default")
      (node (ref "J18") (pin "3") (pinfunction "3_3") (pintype "passive"))
    )
    (net (code "60") (name "unconnected-(J19-Pad8)") (class "Default")
      (node (ref "J19") (pin "8") (pinfunction "8_8") (pintype "bidirectional"))
    )
    (net (code "61") (name "unconnected-(J19-PadMP1)") (class "Default")
      (node (ref "J19") (pin "MP1") (pinfunction "MP1_MP1") (pintype "bidirectional"))
    )
    (net (code "62") (name "unconnected-(J19-PadMP2)") (class "Default")
      (node (ref "J19") (pin "MP2") (pinfunction "MP2_MP2") (pintype "bidirectional"))
    )
    (net (code "63") (name "unconnected-(RTC1-32KHZ-Pad1)") (class "Default")
      (node (ref "RTC1") (pin "1") (pinfunction "32KHZ_1") (pintype "output"))
    )
    (net (code "64") (name "unconnected-(U1-CLK-Pad38)") (class "Default")
      (node (ref "U1") (pin "38") (pinfunction "CLK_38") (pintype "input"))
    )
    (net (code "65") (name "unconnected-(U1-IO0-Pad33)") (class "Default")
      (node (ref "U1") (pin "33") (pinfunction "IO0_33") (pintype "bidirectional"))
    )
    (net (code "66") (name "unconnected-(U1-IO2-Pad34)") (class "Default")
      (node (ref "U1") (pin "34") (pinfunction "IO2_34") (pintype "bidirectional"))
    )
    (net (code "67") (name "unconnected-(U1-RXD0-Pad24)") (class "Default")
      (node (ref "U1") (pin "24") (pinfunction "RXD0_24") (pintype "input"))
    )
    (net (code "68") (name "unconnected-(U1-SD0-Pad37)") (class "Default")
      (node (ref "U1") (pin "37") (pinfunction "SD0_37") (pintype "bidirectional"))
    )
    (net (code "69") (name "unconnected-(U1-SD1-Pad36)") (class "Default")
      (node (ref "U1") (pin "36") (pinfunction "SD1_36") (pintype "bidirectional"))
    )
    (net (code "70") (name "unconnected-(U1-TXD0-Pad23)") (class "Default")
      (node (ref "U1") (pin "23") (pinfunction "TXD0_23") (pintype "output"))
    )
    (net (code "71") (name "unconnected-(VR1-PadMH1)") (class "Default")
      (node (ref "VR1") (pin "MH1") (pinfunction "MH1_MH1") (pintype "bidirectional"))
    )
    (net (code "72") (name "unconnected-(VR1-PadMH2)") (class "Default")
      (node (ref "VR1") (pin "MH2") (pinfunction "MH2_MH2") (pintype "bidirectional"))
    )
    (net (code "73") (name "~{INT}") (class "Default")
      (node (ref "IC2") (pin "13") (pinfunction "~{INT}_13") (pintype "bidirectional"))
      (node (ref "U1") (pin "32") (pinfunction "IO4_32") (pintype "bidirectional"))
    )
    (net (code "74") (name "~{RST}") (class "Default")
      (node (ref "J5") (pin "5") (pinfunction "5_5") (pintype "passive"))
      (node (ref "J9") (pin "18") (pinfunction "18_18") (pintype "passive"))
      (node (ref "RTC1") (pin "4") (pinfunction "RST_4") (pintype "bidirectional"))
      (node (ref "U1") (pin "2") (pinfunction "EN_2") (pintype "input"))
    )
  )
)
